# LaserTag.net
KiCad netlist of a schematic drawn in EasyEDA
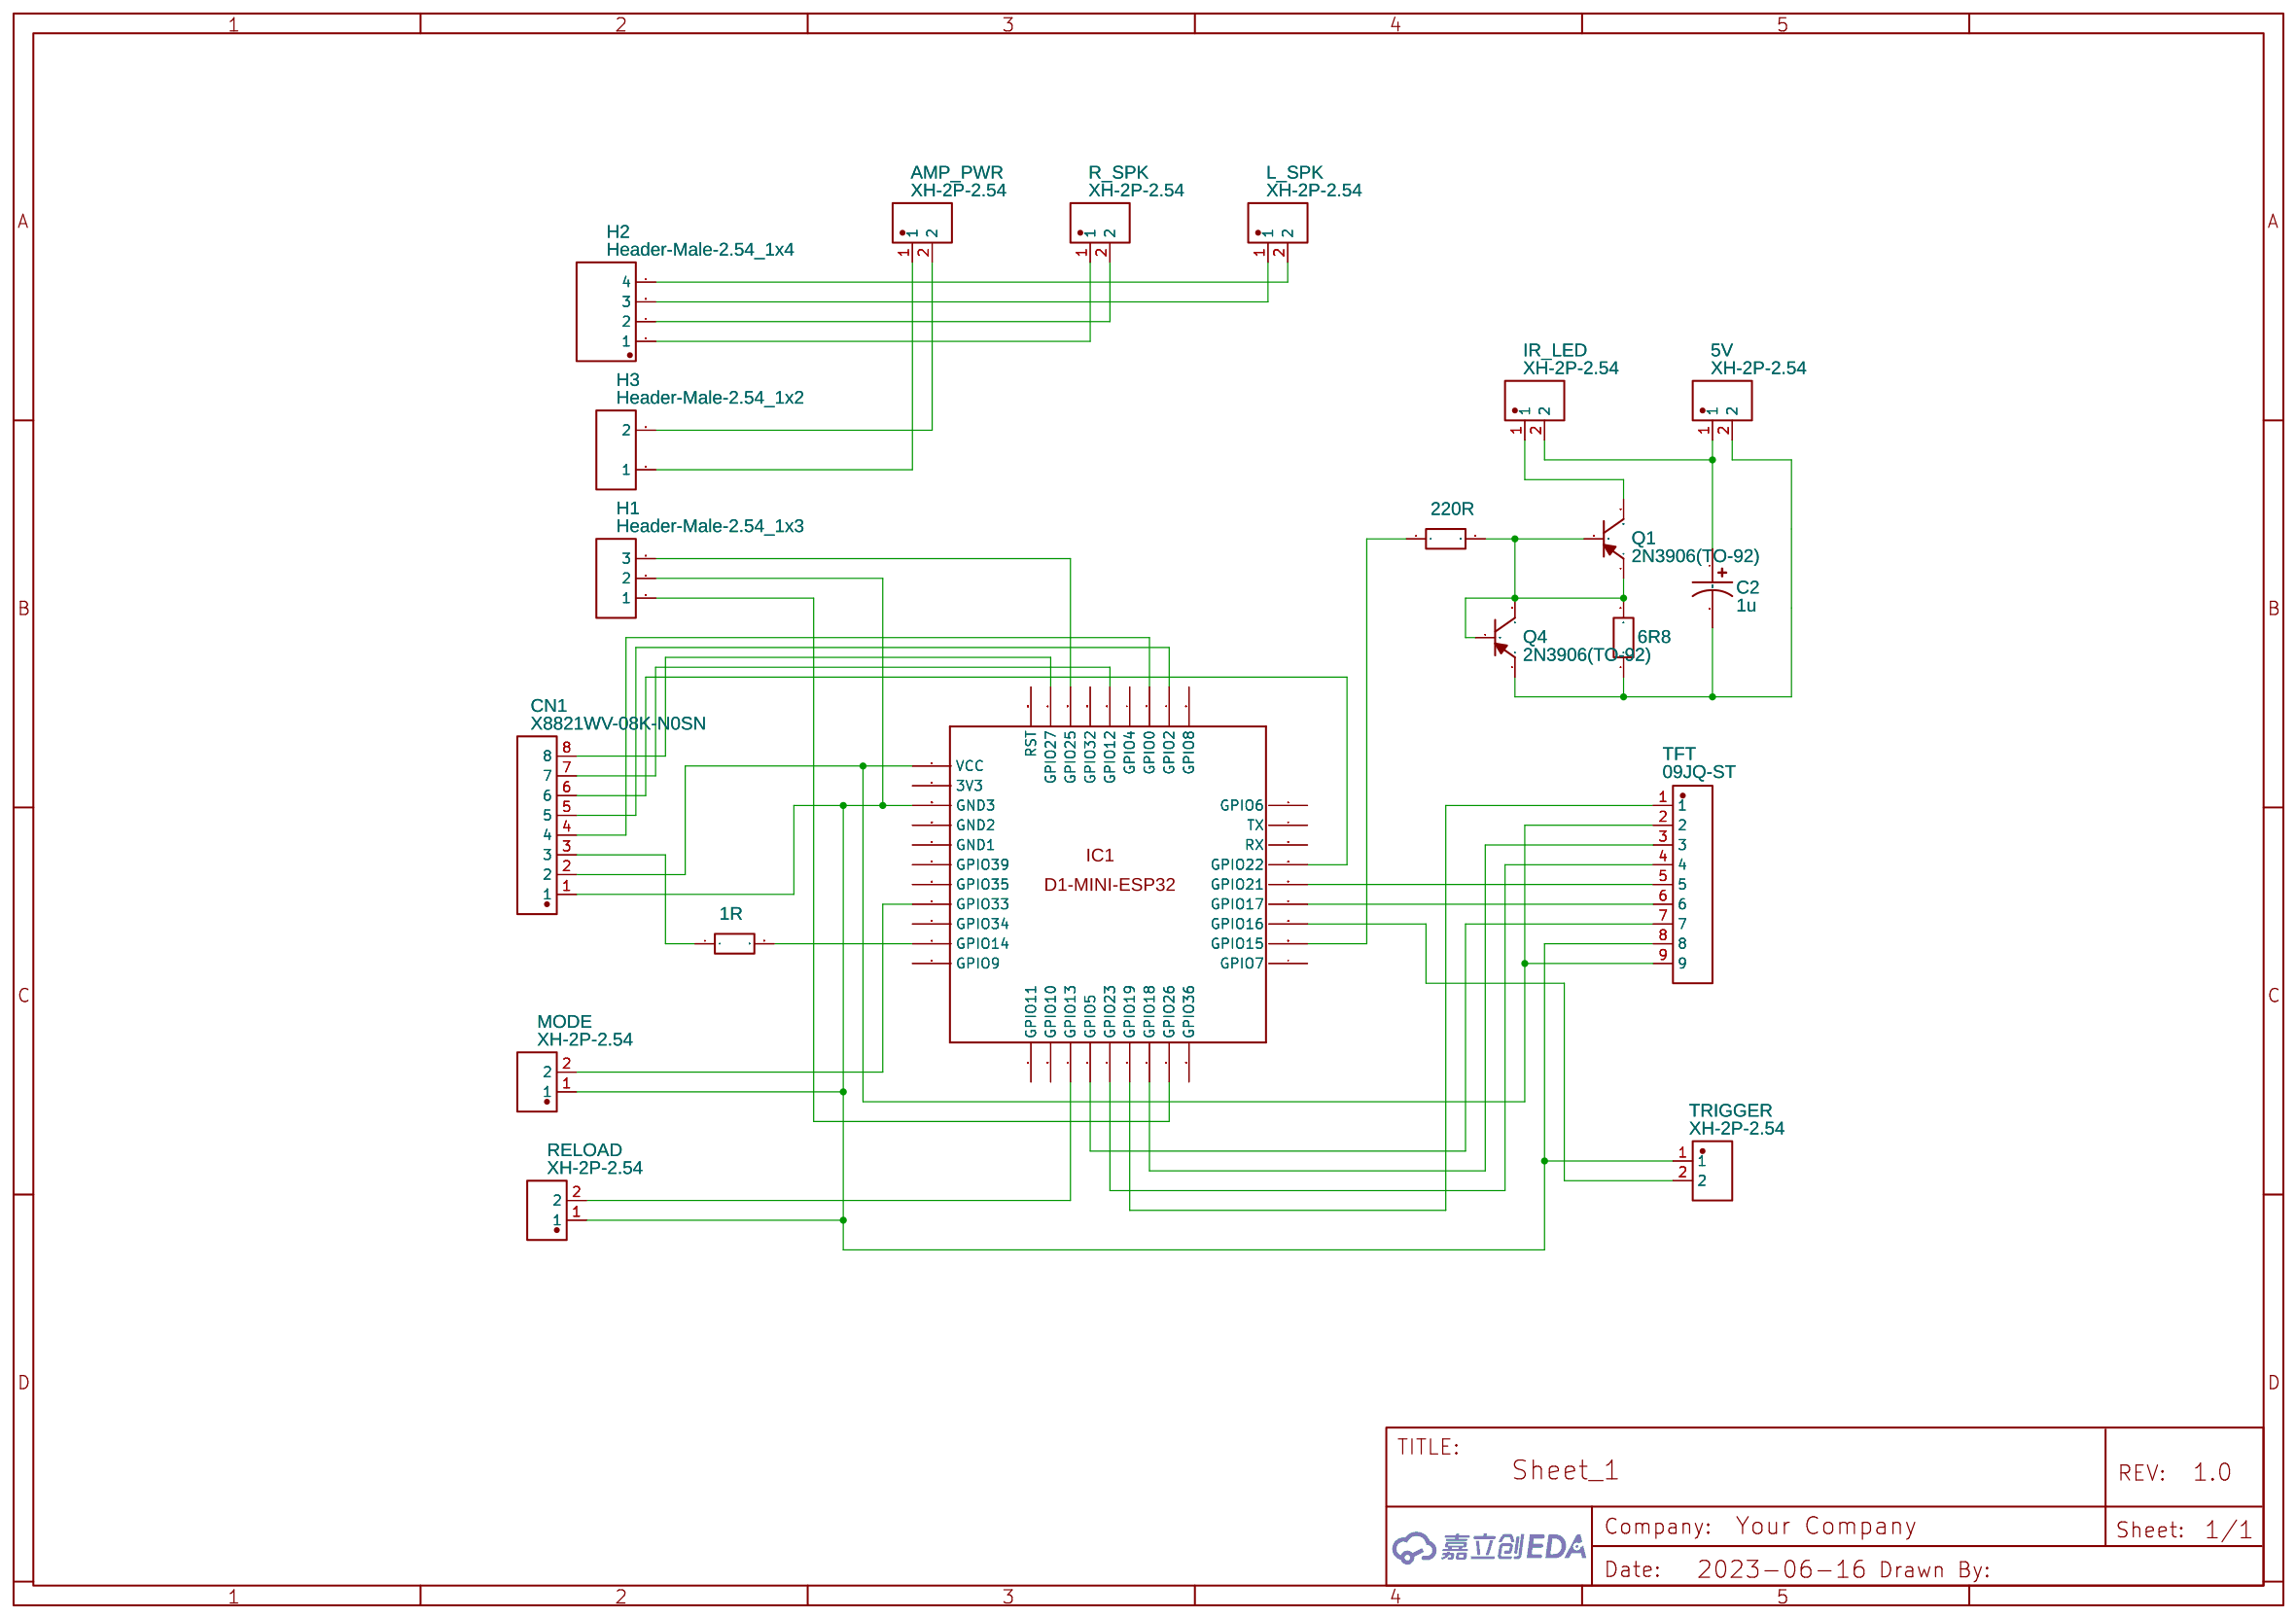
[diagram p0: schematic sheet]

(export (version "E")
  (design (tool "Eeschema 10.0.6"))
  (components
    (comp (ref "1R")
      (value "?")
      (fields
        (field (name "BOM_Manufacturer Part") "MO1/4W-220K±5%-ST52")
        (field (name "BOM_Supplier Part") "C2857428")
      )
      (libsource (lib "") (part "MO1/4W-220K±5%-ST52_1"))
    )
    (comp (ref "5V") (value "XH-2P-2.54") (libsource (lib "") (part "XH-2P-2.54_3")))
    (comp (ref "6R8")
      (value "?")
      (fields
        (field (name "BOM_Manufacturer Part") "MO1/4W-220K±5%-ST52")
        (field (name "BOM_Supplier Part") "C2857428")
      )
      (libsource (lib "") (part "MO1/4W-220K±5%-ST52"))
    )
    (comp (ref "220R")
      (value "?")
      (fields
        (field (name "BOM_Manufacturer Part") "MO1/4W-220K±5%-ST52")
        (field (name "BOM_Supplier Part") "C2857428")
      )
      (libsource (lib "") (part "MO1/4W-220K±5%-ST52_2"))
    )
    (comp (ref "AMP_PWR") (value "XH-2P-2.54") (libsource (lib "") (part "XH-2P-2.54_4")))
    (comp (ref "C2") (value "1u") (libsource (lib "") (part "CE_TH_D6.3×F2.5_US")))
    (comp (ref "CN1")
      (value "X8821WV-08K-N0SN")
      (fields (field (name "Manufacturer") "XKB Connectivity(中国星坤)"))
      (libsource (lib "") (part "X8821WV-08K-N0SN"))
    )
    (comp (ref "H1")
      (value "Header-Male-2.54_1x3")
      (fields (field (name "Manufacturer Part") "2.54-1*3P针") (field (name "Manufacturer") "BOOMELE(博穆精密)"))
      (libsource (lib "") (part "Header-Male-2.54_1x3"))
    )
    (comp (ref "H2")
      (value "Header-Male-2.54_1x4")
      (fields (field (name "Manufacturer Part") "B-2100S04P-A110") (field (name "Manufacturer") "Ckmtw(灿科盟)"))
      (libsource (lib "") (part "Header-Male-2.54_1x4"))
    )
    (comp (ref "H3")
      (value "Header-Male-2.54_1x2")
      (fields
        (field (name "Manufacturer Part") "826629-2")
        (field (name "Manufacturer") "TE Connectivity(美国泰科)")
      )
      (libsource (lib "") (part "Header-Male-2.54_1x2"))
    )
    (comp (ref "IR_LED") (value "XH-2P-2.54") (libsource (lib "") (part "XH-2P-2.54_2")))
    (comp (ref "L_SPK") (value "XH-2P-2.54") (libsource (lib "") (part "XH-2P-2.54_7")))
    (comp (ref "MODE") (value "XH-2P-2.54") (libsource (lib "") (part "XH-2P-2.54")))
    (comp (ref "Q1")
      (value "2N3906(TO-92)")
      (fields (field (name "BOM_Manufacturer Part") "2N3906") (field (name "BOM_Supplier Part") "C9809"))
      (libsource (lib "") (part "2N3906(TO-92)"))
    )
    (comp (ref "Q4")
      (value "2N3906(TO-92)")
      (fields (field (name "BOM_Manufacturer Part") "2N3906") (field (name "BOM_Supplier Part") "C9809"))
      (libsource (lib "") (part "2N3906(TO-92)"))
    )
    (comp (ref "RELOAD") (value "XH-2P-2.54") (libsource (lib "") (part "XH-2P-2.54_1")))
    (comp (ref "R_SPK") (value "XH-2P-2.54") (libsource (lib "") (part "XH-2P-2.54_5")))
    (comp (ref "TFT")
      (value "09JQ-ST")
      (fields (field (name "BOM_Supplier Part") "C5118719"))
      (libsource (lib "") (part "09JQ-ST"))
    )
    (comp (ref "TRIGGER") (value "XH-2P-2.54") (libsource (lib "") (part "XH-2P-2.54_6")))
    (comp (ref "U1") (value "D1-mini-ESP32") (libsource (lib "") (part "D1-mini-ESP32")))
  )
  (nets
    (net (code "1") (name "Net-(1R-Pad1)") (class "Default")
      (node (ref "1R") (pin "1") (pinfunction "1_1") (pintype "unspecified"))
      (node (ref "CN1") (pin "3") (pinfunction "3_3") (pintype "unspecified"))
    )
    (net (code "2") (name "Net-(5V-Pad1)") (class "Default")
      (node (ref "5V") (pin "1") (pinfunction "1_1") (pintype "unspecified"))
      (node (ref "C2") (pin "1") (pinfunction "1_1") (pintype "unspecified"))
      (node (ref "IR_LED") (pin "2") (pinfunction "2_2") (pintype "unspecified"))
    )
    (net (code "3") (name "Net-(AMP_PWR-Pad1)") (class "Default")
      (node (ref "AMP_PWR") (pin "1") (pinfunction "1_1") (pintype "unspecified"))
      (node (ref "H3") (pin "1") (pinfunction "1_1") (pintype "unspecified"))
    )
    (net (code "4") (name "Net-(AMP_PWR-Pad2)") (class "Default")
      (node (ref "AMP_PWR") (pin "2") (pinfunction "2_2") (pintype "unspecified"))
      (node (ref "H3") (pin "2") (pinfunction "2_2") (pintype "unspecified"))
    )
    (net (code "5") (name "Net-(CN1-Pad1)") (class "Default")
      (node (ref "CN1") (pin "1") (pinfunction "1_1") (pintype "unspecified"))
      (node (ref "H1") (pin "2") (pinfunction "2_2") (pintype "input"))
      (node (ref "MODE") (pin "1") (pinfunction "1_1") (pintype "unspecified"))
      (node (ref "RELOAD") (pin "1") (pinfunction "1_1") (pintype "unspecified"))
      (node (ref "TFT") (pin "8") (pinfunction "8_8") (pintype "unspecified"))
      (node (ref "TRIGGER") (pin "1") (pinfunction "1_1") (pintype "unspecified"))
      (node (ref "U1") (pin "GND3") (pinfunction "GND3_GND3") (pintype "bidirectional"))
    )
    (net (code "6") (name "Net-(CN1-Pad2)") (class "Default")
      (node (ref "CN1") (pin "2") (pinfunction "2_2") (pintype "unspecified"))
      (node (ref "TFT") (pin "2") (pinfunction "2_2") (pintype "unspecified"))
      (node (ref "TFT") (pin "9") (pinfunction "9_9") (pintype "unspecified"))
      (node (ref "U1") (pin "VCC") (pinfunction "VCC_VCC") (pintype "bidirectional"))
    )
    (net (code "7") (name "Net-(H2-Pad1)") (class "Default")
      (node (ref "H2") (pin "1") (pinfunction "1_1") (pintype "unspecified"))
      (node (ref "R_SPK") (pin "1") (pinfunction "1_1") (pintype "unspecified"))
    )
    (net (code "8") (name "Net-(H2-Pad2)") (class "Default")
      (node (ref "H2") (pin "2") (pinfunction "2_2") (pintype "unspecified"))
      (node (ref "R_SPK") (pin "2") (pinfunction "2_2") (pintype "unspecified"))
    )
    (net (code "9") (name "Net-(H2-Pad3)") (class "Default")
      (node (ref "H2") (pin "3") (pinfunction "3_3") (pintype "unspecified"))
      (node (ref "L_SPK") (pin "1") (pinfunction "1_1") (pintype "unspecified"))
    )
    (net (code "10") (name "Net-(H2-Pad4)") (class "Default")
      (node (ref "H2") (pin "4") (pinfunction "4_4") (pintype "unspecified"))
      (node (ref "L_SPK") (pin "2") (pinfunction "2_2") (pintype "unspecified"))
    )
    (net (code "11") (name "Net-(Q1-B)") (class "Default")
      (node (ref "220R") (pin "2") (pinfunction "2_2") (pintype "unspecified"))
      (node (ref "6R8") (pin "2") (pinfunction "2_2") (pintype "unspecified"))
      (node (ref "Q1") (pin "1") (pinfunction "E_1") (pintype "input"))
      (node (ref "Q1") (pin "2") (pinfunction "B_2") (pintype "input"))
      (node (ref "Q4") (pin "2") (pinfunction "B_2") (pintype "input"))
      (node (ref "Q4") (pin "3") (pinfunction "C_3") (pintype "input"))
    )
    (net (code "12") (name "Net-(Q1-C)") (class "Default")
      (node (ref "IR_LED") (pin "1") (pinfunction "1_1") (pintype "unspecified"))
      (node (ref "Q1") (pin "3") (pinfunction "C_3") (pintype "input"))
    )
    (net (code "13") (name "Net-(Q4-E)") (class "Default")
      (node (ref "5V") (pin "2") (pinfunction "2_2") (pintype "unspecified"))
      (node (ref "6R8") (pin "1") (pinfunction "1_1") (pintype "unspecified"))
      (node (ref "C2") (pin "2") (pinfunction "2_2") (pintype "unspecified"))
      (node (ref "Q4") (pin "1") (pinfunction "E_1") (pintype "input"))
    )
    (net (code "14") (name "Net-(U1-GPIO0)") (class "Default")
      (node (ref "CN1") (pin "4") (pinfunction "4_4") (pintype "unspecified"))
      (node (ref "U1") (pin "0") (pinfunction "GPIO0_0") (pintype "bidirectional"))
    )
    (net (code "15") (name "Net-(U1-GPIO2)") (class "Default")
      (node (ref "CN1") (pin "5") (pinfunction "5_5") (pintype "unspecified"))
      (node (ref "U1") (pin "2") (pinfunction "GPIO2_2") (pintype "bidirectional"))
    )
    (net (code "16") (name "Net-(U1-GPIO5)") (class "Default")
      (node (ref "TFT") (pin "7") (pinfunction "7_7") (pintype "unspecified"))
      (node (ref "U1") (pin "5") (pinfunction "GPIO5_5") (pintype "bidirectional"))
    )
    (net (code "17") (name "Net-(U1-GPIO12)") (class "Default")
      (node (ref "CN1") (pin "7") (pinfunction "7_7") (pintype "unspecified"))
      (node (ref "U1") (pin "12") (pinfunction "GPIO12_12") (pintype "bidirectional"))
    )
    (net (code "18") (name "Net-(U1-GPIO13)") (class "Default")
      (node (ref "RELOAD") (pin "2") (pinfunction "2_2") (pintype "unspecified"))
      (node (ref "U1") (pin "13") (pinfunction "GPIO13_13") (pintype "bidirectional"))
    )
    (net (code "19") (name "Net-(U1-GPIO14)") (class "Default")
      (node (ref "1R") (pin "2") (pinfunction "2_2") (pintype "unspecified"))
      (node (ref "U1") (pin "14") (pinfunction "GPIO14_14") (pintype "bidirectional"))
    )
    (net (code "20") (name "Net-(U1-GPIO15)") (class "Default")
      (node (ref "220R") (pin "1") (pinfunction "1_1") (pintype "unspecified"))
      (node (ref "U1") (pin "15") (pinfunction "GPIO15_15") (pintype "bidirectional"))
    )
    (net (code "21") (name "Net-(U1-GPIO16)") (class "Default")
      (node (ref "TRIGGER") (pin "2") (pinfunction "2_2") (pintype "unspecified"))
      (node (ref "U1") (pin "16") (pinfunction "GPIO16_16") (pintype "bidirectional"))
    )
    (net (code "22") (name "Net-(U1-GPIO17)") (class "Default")
      (node (ref "TFT") (pin "6") (pinfunction "6_6") (pintype "unspecified"))
      (node (ref "U1") (pin "17") (pinfunction "GPIO17_17") (pintype "bidirectional"))
    )
    (net (code "23") (name "Net-(U1-GPIO18)") (class "Default")
      (node (ref "TFT") (pin "3") (pinfunction "3_3") (pintype "unspecified"))
      (node (ref "U1") (pin "18") (pinfunction "GPIO18_18") (pintype "bidirectional"))
    )
    (net (code "24") (name "Net-(U1-GPIO19)") (class "Default")
      (node (ref "TFT") (pin "1") (pinfunction "1_1") (pintype "unspecified"))
      (node (ref "U1") (pin "19") (pinfunction "GPIO19_19") (pintype "bidirectional"))
    )
    (net (code "25") (name "Net-(U1-GPIO21)") (class "Default")
      (node (ref "TFT") (pin "5") (pinfunction "5_5") (pintype "unspecified"))
      (node (ref "U1") (pin "21") (pinfunction "GPIO21_21") (pintype "bidirectional"))
    )
    (net (code "26") (name "Net-(U1-GPIO22)") (class "Default")
      (node (ref "CN1") (pin "6") (pinfunction "6_6") (pintype "unspecified"))
      (node (ref "U1") (pin "22") (pinfunction "GPIO22_22") (pintype "bidirectional"))
    )
    (net (code "27") (name "Net-(U1-GPIO23)") (class "Default")
      (node (ref "TFT") (pin "4") (pinfunction "4_4") (pintype "unspecified"))
      (node (ref "U1") (pin "23") (pinfunction "GPIO23_23") (pintype "bidirectional"))
    )
    (net (code "28") (name "Net-(U1-GPIO25)") (class "Default")
      (node (ref "H1") (pin "3") (pinfunction "3_3") (pintype "input"))
      (node (ref "U1") (pin "25") (pinfunction "GPIO25_25") (pintype "bidirectional"))
    )
    (net (code "29") (name "Net-(U1-GPIO26)") (class "Default")
      (node (ref "H1") (pin "1") (pinfunction "1_1") (pintype "input"))
      (node (ref "U1") (pin "26") (pinfunction "GPIO26_26") (pintype "bidirectional"))
    )
    (net (code "30") (name "Net-(U1-GPIO27)") (class "Default")
      (node (ref "CN1") (pin "8") (pinfunction "8_8") (pintype "unspecified"))
      (node (ref "U1") (pin "27") (pinfunction "GPIO27_27") (pintype "bidirectional"))
    )
    (net (code "31") (name "Net-(U1-GPIO33)") (class "Default")
      (node (ref "MODE") (pin "2") (pinfunction "2_2") (pintype "unspecified"))
      (node (ref "U1") (pin "33") (pinfunction "GPIO33_33") (pintype "bidirectional"))
    )
    (net (code "32") (name "unconnected-(U1-GPIO4-Pad4)") (class "Default")
      (node (ref "U1") (pin "4") (pinfunction "GPIO4_4") (pintype "bidirectional"))
    )
    (net (code "33") (name "unconnected-(U1-GPIO6-Pad6)") (class "Default")
      (node (ref "U1") (pin "6") (pinfunction "GPIO6_6") (pintype "bidirectional"))
    )
    (net (code "34") (name "unconnected-(U1-GPIO7-Pad7)") (class "Default")
      (node (ref "U1") (pin "7") (pinfunction "GPIO7_7") (pintype "bidirectional"))
    )
    (net (code "35") (name "unconnected-(U1-GPIO8-Pad8)") (class "Default")
      (node (ref "U1") (pin "8") (pinfunction "GPIO8_8") (pintype "bidirectional"))
    )
    (net (code "36") (name "unconnected-(U1-GPIO9-Pad9)") (class "Default")
      (node (ref "U1") (pin "9") (pinfunction "GPIO9_9") (pintype "bidirectional"))
    )
    (net (code "37") (name "unconnected-(U1-GPIO10-Pad10)") (class "Default")
      (node (ref "U1") (pin "10") (pinfunction "GPIO10_10") (pintype "bidirectional"))
    )
    (net (code "38") (name "unconnected-(U1-GPIO11-Pad11)") (class "Default")
      (node (ref "U1") (pin "11") (pinfunction "GPIO11_11") (pintype "bidirectional"))
    )
    (net (code "39") (name "unconnected-(U1-GPIO32-Pad32)") (class "Default")
      (node (ref "U1") (pin "32") (pinfunction "GPIO32_32") (pintype "bidirectional"))
    )
    (net (code "40") (name "unconnected-(U1-GPIO34-Pad34)") (class "Default")
      (node (ref "U1") (pin "34") (pinfunction "GPIO34_34") (pintype "bidirectional"))
    )
    (net (code "41") (name "unconnected-(U1-GPIO35-Pad35)") (class "Default")
      (node (ref "U1") (pin "35") (pinfunction "GPIO35_35") (pintype "bidirectional"))
    )
    (net (code "42") (name "unconnected-(U1-GPIO36-Pad36)") (class "Default")
      (node (ref "U1") (pin "36") (pinfunction "GPIO36_36") (pintype "bidirectional"))
    )
    (net (code "43") (name "unconnected-(U1-GPIO39-Pad39)") (class "Default")
      (node (ref "U1") (pin "39") (pinfunction "GPIO39_39") (pintype "bidirectional"))
    )
    (net (code "44") (name "unconnected-(U1-Pad3V3)") (class "Default")
      (node (ref "U1") (pin "3V3") (pinfunction "3V3_3V3") (pintype "bidirectional"))
    )
    (net (code "45") (name "unconnected-(U1-PadGND1)") (class "Default")
      (node (ref "U1") (pin "GND1") (pinfunction "GND1_GND1") (pintype "bidirectional"))
    )
    (net (code "46") (name "unconnected-(U1-PadGND2)") (class "Default")
      (node (ref "U1") (pin "GND2") (pinfunction "GND2_GND2") (pintype "bidirectional"))
    )
    (net (code "47") (name "unconnected-(U1-PadRST)") (class "Default")
      (node (ref "U1") (pin "RST") (pinfunction "RST_RST") (pintype "bidirectional"))
    )
    (net (code "48") (name "unconnected-(U1-PadRX)") (class "Default")
      (node (ref "U1") (pin "RX") (pinfunction "RX_RX") (pintype "bidirectional"))
    )
    (net (code "49") (name "unconnected-(U1-PadTX)") (class "Default")
      (node (ref "U1") (pin "TX") (pinfunction "TX_TX") (pintype "bidirectional"))
    )
  )
)
